# Fri3D_IRA_ESP32.net
KiCad netlist of a schematic drawn in Altium Designer
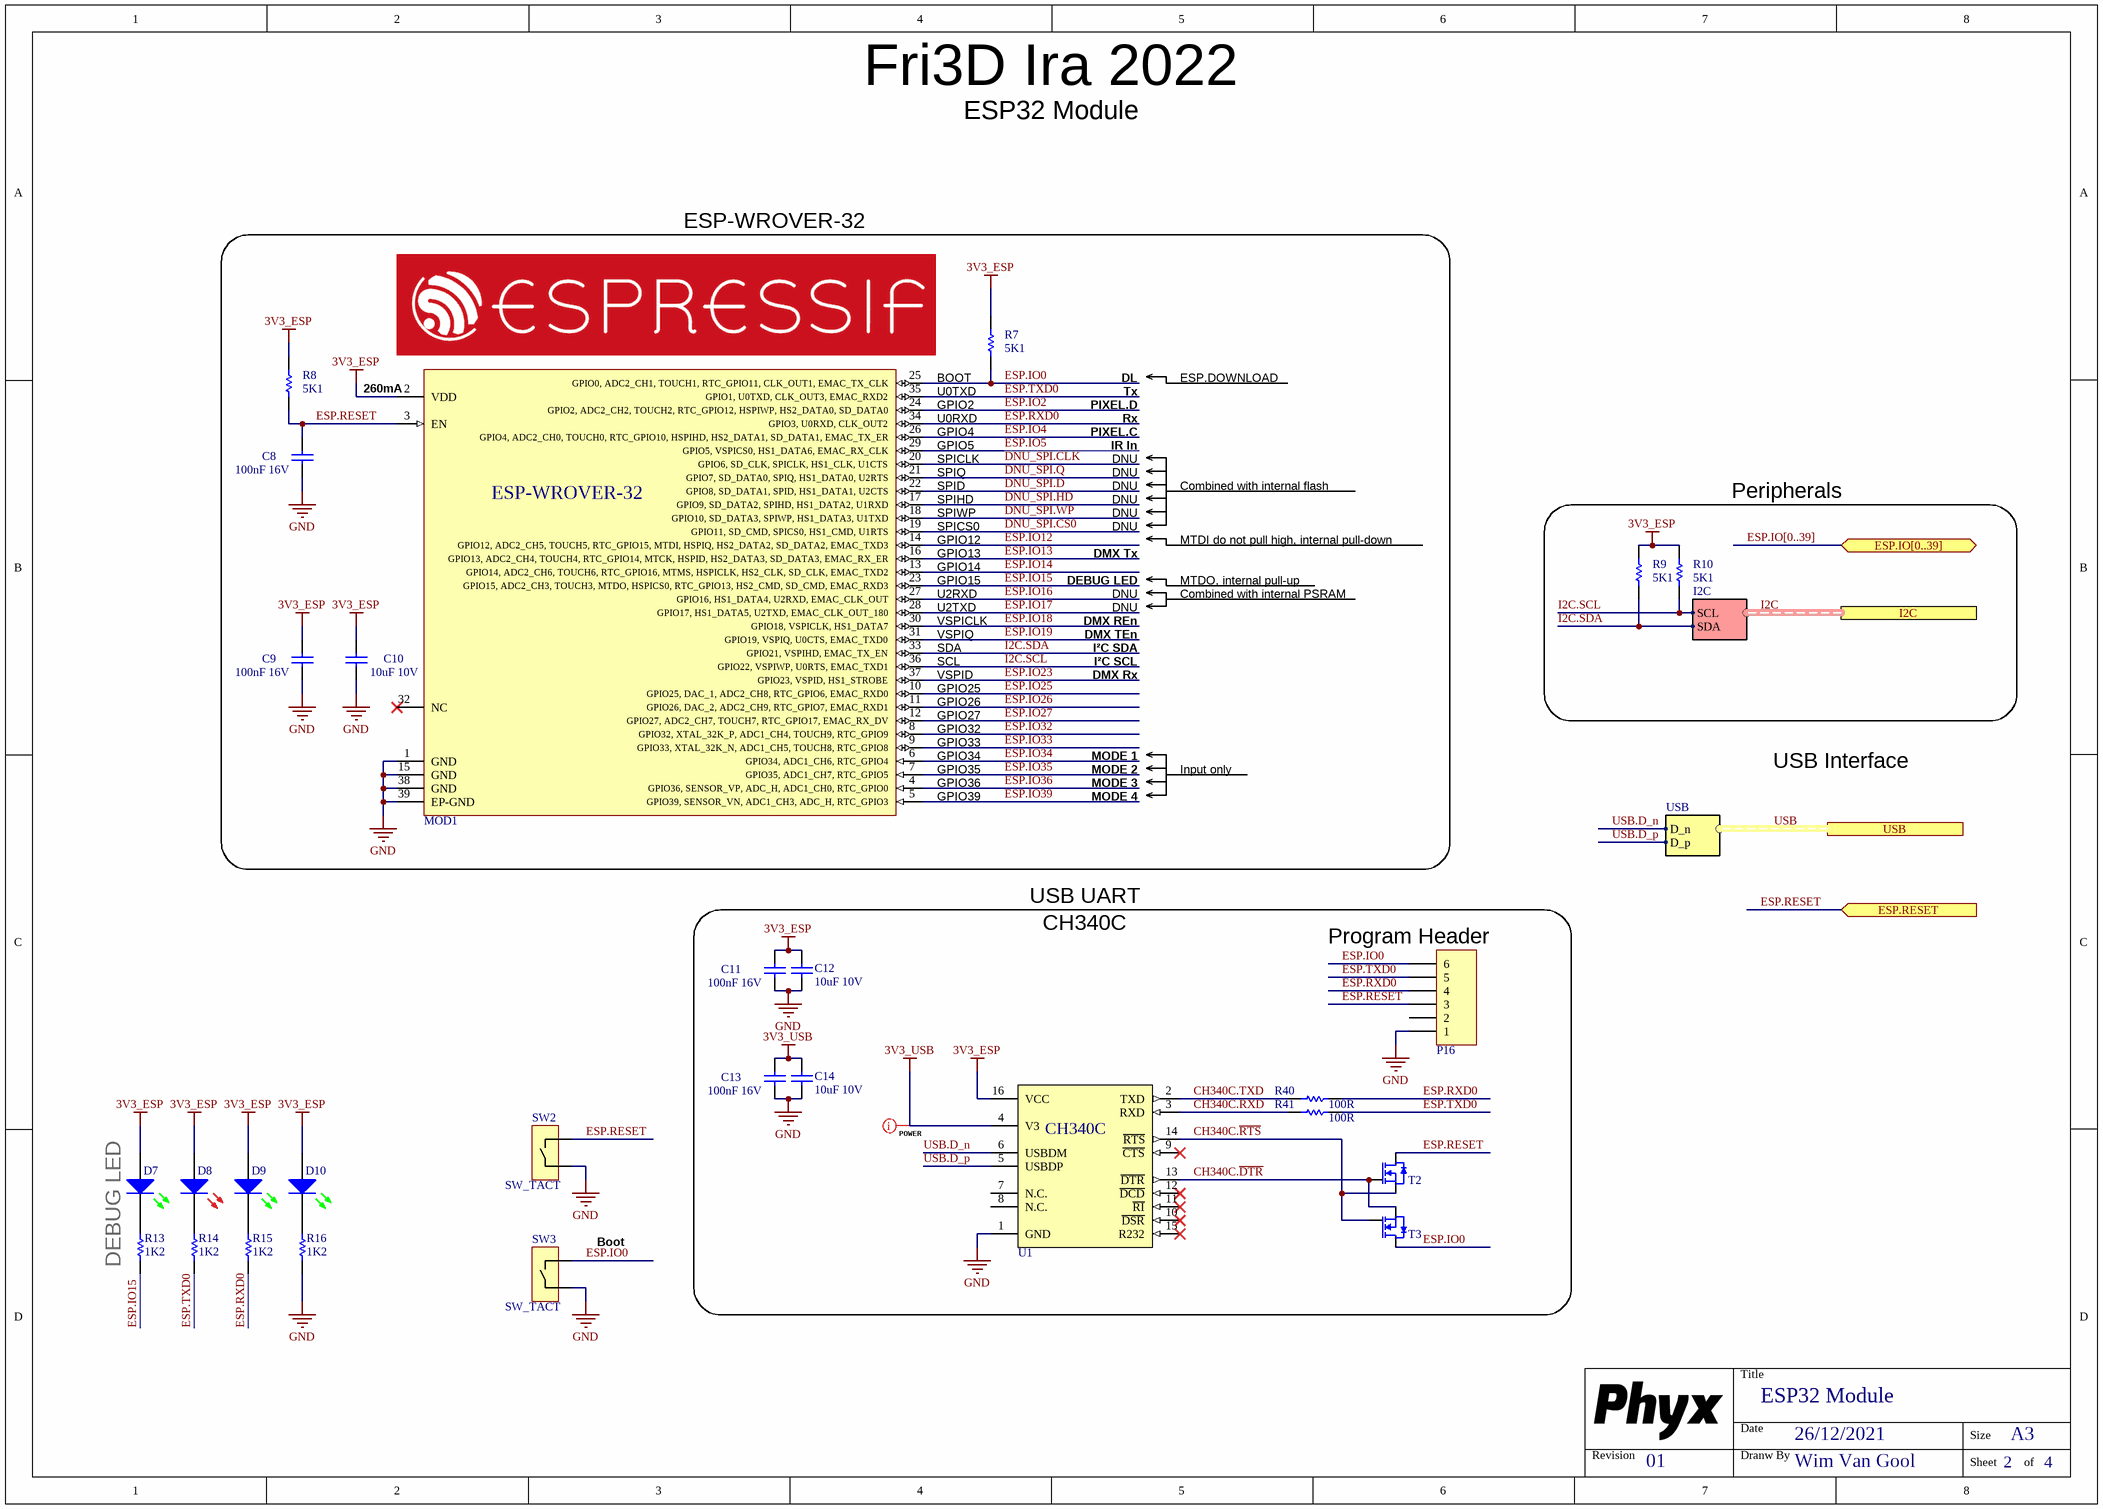
[diagram p0: Fri3D_IRA_ESP32.SchDoc]

(export (version "E")
  (design (tool "Eeschema 10.0.6"))
  (components
    (comp (ref "C8")
      (value "100nF 16V")
      (footprint "C0603_N")
      (description "Capacitor Ceramic")
      (libsource (lib "Phyx_Components") (part "CAP_CERAMIC"))
    )
    (comp (ref "C9")
      (value "100nF 16V")
      (footprint "C0603_N")
      (description "Capacitor Ceramic")
      (libsource (lib "Phyx_Components") (part "CAP_CERAMIC"))
    )
    (comp (ref "C10")
      (value "10uF 10V")
      (footprint "C0805_N")
      (description "Capacitor Ceramic")
      (fields (field (name "Comment") "CAP_CERAMIC"))
      (libsource (lib "Phyx_Components") (part "CAP_CERAMIC"))
    )
    (comp (ref "C11")
      (value "100nF 16V")
      (footprint "C0603_N")
      (description "Capacitor Ceramic")
      (libsource (lib "Phyx_Components") (part "CAP_CERAMIC"))
    )
    (comp (ref "C12")
      (value "10uF 10V")
      (footprint "C0805_N")
      (description "Capacitor Ceramic")
      (fields (field (name "Comment") "CAP_CERAMIC"))
      (libsource (lib "Phyx_Components") (part "CAP_CERAMIC"))
    )
    (comp (ref "C13")
      (value "100nF 16V")
      (footprint "C0603_N")
      (description "Capacitor Ceramic")
      (libsource (lib "Phyx_Components") (part "CAP_CERAMIC"))
    )
    (comp (ref "C14")
      (value "10uF 10V")
      (footprint "C0805_N")
      (description "Capacitor Ceramic")
      (fields (field (name "Comment") "CAP_CERAMIC"))
      (libsource (lib "Phyx_Components") (part "CAP_CERAMIC"))
    )
    (comp (ref "D7")
      (value "Default 0805 Green LED")
      (footprint "LED_0805_GR")
      (description "=Description")
      (libsource (lib "Phyx_Components") (part "LED_GREEN"))
    )
    (comp (ref "D8")
      (value "Default 0805 Red LED")
      (footprint "LED_0805_RD")
      (description "=Description")
      (libsource (lib "Phyx_Components") (part "LED_RED"))
    )
    (comp (ref "D9")
      (value "Default 0805 Green LED")
      (footprint "LED_0805_GR")
      (description "=Description")
      (libsource (lib "Phyx_Components") (part "LED_GREEN"))
    )
    (comp (ref "D10")
      (value "Default 0805 Green LED")
      (footprint "LED_0805_GR")
      (description "=Description")
      (libsource (lib "Phyx_Components") (part "LED_GREEN"))
    )
    (comp (ref "MOD1")
      (value "ESP-32 based ESP-WROVER-32")
      (footprint "ESP-WROVER-32")
      (description "WiFi # MOD ESP-WROVER-32")
      (libsource (lib "Phyx_Components") (part "ESP-WROVER-32"))
    )
    (comp (ref "P16")
      (value "Header 6")
      (footprint "HDR1X6")
      (libsource (lib "Phyx_Components") (part "Header 6"))
    )
    (comp (ref "R7")
      (value "5K1")
      (footprint "R0603_N")
      (fields (field (name "Comment") "RESISTOR"))
      (libsource (lib "Phyx_Components") (part "RESISTOR"))
    )
    (comp (ref "R8")
      (value "5K1")
      (footprint "R0603_N")
      (fields (field (name "Comment") "RESISTOR"))
      (libsource (lib "Phyx_Components") (part "RESISTOR"))
    )
    (comp (ref "R9")
      (value "5K1")
      (footprint "R0603_N")
      (fields (field (name "Comment") "RESISTOR"))
      (libsource (lib "Phyx_Components") (part "RESISTOR"))
    )
    (comp (ref "R10")
      (value "5K1")
      (footprint "R0603_N")
      (fields (field (name "Comment") "RESISTOR"))
      (libsource (lib "Phyx_Components") (part "RESISTOR"))
    )
    (comp (ref "R13")
      (value "1K2")
      (footprint "R0603_N")
      (fields (field (name "Comment") "RESISTOR"))
      (libsource (lib "Phyx_Components") (part "RESISTOR"))
    )
    (comp (ref "R14")
      (value "1K2")
      (footprint "R0603_N")
      (fields (field (name "Comment") "RESISTOR"))
      (libsource (lib "Phyx_Components") (part "RESISTOR"))
    )
    (comp (ref "R15")
      (value "1K2")
      (footprint "R0603_N")
      (fields (field (name "Comment") "RESISTOR"))
      (libsource (lib "Phyx_Components") (part "RESISTOR"))
    )
    (comp (ref "R16")
      (value "1K2")
      (footprint "R0603_N")
      (fields (field (name "Comment") "RESISTOR"))
      (libsource (lib "Phyx_Components") (part "RESISTOR"))
    )
    (comp (ref "R40")
      (value "100R")
      (footprint "R0603_N")
      (fields (field (name "Comment") "RESISTOR"))
      (libsource (lib "Phyx_Components") (part "RESISTOR"))
    )
    (comp (ref "R41")
      (value "100R")
      (footprint "R0603_N")
      (fields (field (name "Comment") "RESISTOR"))
      (libsource (lib "Phyx_Components") (part "RESISTOR"))
    )
    (comp (ref "SW2")
      (value "SW_TACT")
      (footprint "WE_430181038816")
      (libsource (lib "Phyx_Components") (part "SW_TACT"))
    )
    (comp (ref "SW3")
      (value "SW_TACT")
      (footprint "WE_430181038816")
      (libsource (lib "Phyx_Components") (part "SW_TACT"))
    )
    (comp (ref "T2")
      (value "0.2A N-Ch MOSFET Vgs 3.2")
      (footprint "SOT23-3")
      (libsource (lib "Phyx_Components") (part "N_MOSFET_GSD"))
    )
    (comp (ref "T3")
      (value "0.2A N-Ch MOSFET Vgs 3.2")
      (footprint "SOT23-3")
      (libsource (lib "Phyx_Components") (part "N_MOSFET_GSD"))
    )
    (comp (ref "U1")
      (value "USB to full UART with internal crystal")
      (footprint "SOIC_N_16")
      (description "=Description")
      (libsource (lib "Phyx_Components") (part "CH340C"))
    )
  )
  (nets
    (net (code "21") (name "/CH340C.RXD") (class "Default")
      (node (ref "R41") (pin "1") (pinfunction "1_1") (pintype "passive"))
      (node (ref "U1") (pin "3") (pinfunction "RXD_3") (pintype "input"))
    )
    (net (code "22") (name "/CH340C.TXD") (class "Default")
      (node (ref "R40") (pin "1") (pinfunction "1_1") (pintype "passive"))
      (node (ref "U1") (pin "2") (pinfunction "TXD_2") (pintype "output"))
    )
    (net (code "23") (name "/CH340C.~{DTR}") (class "Default")
      (node (ref "T2") (pin "1") (pinfunction "G_1") (pintype "passive"))
      (node (ref "T3") (pin "2") (pinfunction "S_2") (pintype "passive"))
      (node (ref "U1") (pin "13") (pinfunction "~{DTR}_13") (pintype "output"))
    )
    (net (code "24") (name "/CH340C.~{RTS}") (class "Default")
      (node (ref "T2") (pin "2") (pinfunction "S_2") (pintype "passive"))
      (node (ref "T3") (pin "1") (pinfunction "G_1") (pintype "passive"))
      (node (ref "U1") (pin "14") (pinfunction "~{RTS}_14") (pintype "output"))
    )
    (net (code "25") (name "/DNU_SPI.CLK") (class "Default")
      (node (ref "MOD1") (pin "20") (pinfunction "GPIO6,_SD_CLK,_SPICLK,_HS1_CLK,_U1CTS_20") (pintype "bidirectional"))
    )
    (net (code "26") (name "/DNU_SPI.CS0") (class "Default")
      (node (ref "MOD1") (pin "19") (pinfunction "GPIO11,_SD_CMD,_SPICS0,_HS1_CMD,_U1RTS_19") (pintype "bidirectional"))
    )
    (net (code "27") (name "/DNU_SPI.D") (class "Default")
      (node (ref "MOD1") (pin "22") (pinfunction "GPIO8,_SD_DATA1,_SPID,_HS1_DATA1,_U2CTS_22") (pintype "bidirectional"))
    )
    (net (code "28") (name "/DNU_SPI.HD") (class "Default")
      (node (ref "MOD1") (pin "17") (pinfunction "GPIO9,_SD_DATA2,_SPIHD,_HS1_DATA2,_U1RXD_17") (pintype "bidirectional"))
    )
    (net (code "29") (name "/DNU_SPI.Q") (class "Default")
      (node (ref "MOD1") (pin "21") (pinfunction "GPIO7,_SD_DATA0,_SPIQ,_HS1_DATA0,_U2RTS_21") (pintype "bidirectional"))
    )
    (net (code "30") (name "/DNU_SPI.WP") (class "Default")
      (node (ref "MOD1") (pin "18") (pinfunction "GPIO10,_SD_DATA3,_SPIWP,_HS1_DATA3,_U1TXD_18") (pintype "bidirectional"))
    )
    (net (code "31") (name "/ESP.IO0") (class "Default")
      (node (ref "MOD1") (pin "25") (pinfunction "GPIO0,_ADC2_CH1,_TOUCH1,_RTC_GPIO11,_CLK_OUT1,_EMAC_TX_CLK_25") (pintype "bidirectional"))
      (node (ref "P16") (pin "6") (pinfunction "6_6") (pintype "passive"))
      (node (ref "R7") (pin "2") (pinfunction "2_2") (pintype "passive"))
      (node (ref "SW3") (pin "1") (pinfunction "1_1") (pintype "passive"))
      (node (ref "T3") (pin "3") (pinfunction "D_3") (pintype "passive"))
    )
    (net (code "32") (name "/ESP.IO2") (class "Default")
      (node (ref "MOD1") (pin "24") (pinfunction "GPIO2,_ADC2_CH2,_TOUCH2,_RTC_GPIO12,_HSPIWP,_HS2_DATA0,_SD_DATA0_24") (pintype "bidirectional"))
    )
    (net (code "33") (name "/ESP.IO4") (class "Default")
      (node (ref "MOD1") (pin "26") (pinfunction "GPIO4,_ADC2_CH0,_TOUCH0,_RTC_GPIO10,_HSPIHD,_HS2_DATA1,_SD_DATA1,_EMAC_TX_ER_26") (pintype "bidirectional"))
    )
    (net (code "34") (name "/ESP.IO5") (class "Default")
      (node (ref "MOD1") (pin "29") (pinfunction "GPIO5,_VSPICS0,_HS1_DATA6,_EMAC_RX_CLK_29") (pintype "bidirectional"))
    )
    (net (code "35") (name "/ESP.IO12") (class "Default")
      (node (ref "MOD1") (pin "14") (pinfunction "GPIO12,_ADC2_CH5,_TOUCH5,_RTC_GPIO15,_MTDI,_HSPIQ,_HS2_DATA2,_SD_DATA2,_EMAC_TXD3_14") (pintype "bidirectional"))
    )
    (net (code "36") (name "/ESP.IO13") (class "Default")
      (node (ref "MOD1") (pin "16") (pinfunction "GPIO13,_ADC2_CH4,_TOUCH4,_RTC_GPIO14,_MTCK,_HSPID,_HS2_DATA3,_SD_DATA3,_EMAC_RX_ER_16") (pintype "bidirectional"))
    )
    (net (code "37") (name "/ESP.IO14") (class "Default")
      (node (ref "MOD1") (pin "13") (pinfunction "GPIO14,_ADC2_CH6,_TOUCH6,_RTC_GPIO16,_MTMS,_HSPICLK,_HS2_CLK,_SD_CLK,_EMAC_TXD2_13") (pintype "bidirectional"))
    )
    (net (code "38") (name "/ESP.IO15") (class "Default")
      (node (ref "MOD1") (pin "23") (pinfunction "GPIO15,_ADC2_CH3,_TOUCH3,_MTDO,_HSPICS0,_RTC_GPIO13,_HS2_CMD,_SD_CMD,_EMAC_RXD3_23") (pintype "bidirectional"))
      (node (ref "R13") (pin "2") (pinfunction "2_2") (pintype "passive"))
    )
    (net (code "39") (name "/ESP.IO16") (class "Default")
      (node (ref "MOD1") (pin "27") (pinfunction "GPIO16,_HS1_DATA4,_U2RXD,_EMAC_CLK_OUT_27") (pintype "bidirectional"))
    )
    (net (code "40") (name "/ESP.IO17") (class "Default")
      (node (ref "MOD1") (pin "28") (pinfunction "GPIO17,_HS1_DATA5,_U2TXD,_EMAC_CLK_OUT_180_28") (pintype "bidirectional"))
    )
    (net (code "41") (name "/ESP.IO18") (class "Default")
      (node (ref "MOD1") (pin "30") (pinfunction "GPIO18,_VSPICLK,_HS1_DATA7_30") (pintype "bidirectional"))
    )
    (net (code "42") (name "/ESP.IO19") (class "Default")
      (node (ref "MOD1") (pin "31") (pinfunction "GPIO19,_VSPIQ,_U0CTS,_EMAC_TXD0_31") (pintype "bidirectional"))
    )
    (net (code "43") (name "/ESP.IO23") (class "Default")
      (node (ref "MOD1") (pin "37") (pinfunction "GPIO23,_VSPID,_HS1_STROBE_37") (pintype "bidirectional"))
    )
    (net (code "44") (name "/ESP.IO25") (class "Default")
      (node (ref "MOD1") (pin "10") (pinfunction "GPIO25,_DAC_1,_ADC2_CH8,_RTC_GPIO6,_EMAC_RXD0_10") (pintype "bidirectional"))
    )
    (net (code "45") (name "/ESP.IO26") (class "Default")
      (node (ref "MOD1") (pin "11") (pinfunction "GPIO26,_DAC_2,_ADC2_CH9,_RTC_GPIO7,_EMAC_RXD1_11") (pintype "bidirectional"))
    )
    (net (code "46") (name "/ESP.IO27") (class "Default")
      (node (ref "MOD1") (pin "12") (pinfunction "GPIO27,_ADC2_CH7,_TOUCH7,_RTC_GPIO17,_EMAC_RX_DV_12") (pintype "bidirectional"))
    )
    (net (code "47") (name "/ESP.IO32") (class "Default")
      (node (ref "MOD1") (pin "8") (pinfunction "GPIO32,_XTAL_32K_P,_ADC1_CH4,_TOUCH9,_RTC_GPIO9_8") (pintype "bidirectional"))
    )
    (net (code "48") (name "/ESP.IO33") (class "Default")
      (node (ref "MOD1") (pin "9") (pinfunction "GPIO33,_XTAL_32K_N,_ADC1_CH5,_TOUCH8,_RTC_GPIO8_9") (pintype "bidirectional"))
    )
    (net (code "49") (name "/ESP.IO34") (class "Default")
      (node (ref "MOD1") (pin "6") (pinfunction "GPIO34,_ADC1_CH6,_RTC_GPIO4_6") (pintype "input"))
    )
    (net (code "50") (name "/ESP.IO35") (class "Default")
      (node (ref "MOD1") (pin "7") (pinfunction "GPIO35,_ADC1_CH7,_RTC_GPIO5_7") (pintype "input"))
    )
    (net (code "51") (name "/ESP.IO36") (class "Default")
      (node (ref "MOD1") (pin "4") (pinfunction "GPIO36,_SENSOR_VP,_ADC_H,_ADC1_CH0,_RTC_GPIO0_4") (pintype "input"))
    )
    (net (code "52") (name "/ESP.IO39") (class "Default")
      (node (ref "MOD1") (pin "5") (pinfunction "GPIO39,_SENSOR_VN,_ADC1_CH3,_ADC_H,_RTC_GPIO3_5") (pintype "input"))
    )
    (net (code "54") (name "/ESP.RESET") (class "Default")
      (node (ref "C8") (pin "1") (pinfunction "1_1") (pintype "passive"))
      (node (ref "MOD1") (pin "3") (pinfunction "EN_3") (pintype "input"))
      (node (ref "P16") (pin "3") (pinfunction "3_3") (pintype "passive"))
      (node (ref "R8") (pin "2") (pinfunction "2_2") (pintype "passive"))
      (node (ref "SW2") (pin "1") (pinfunction "1_1") (pintype "passive"))
      (node (ref "T2") (pin "3") (pinfunction "D_3") (pintype "passive"))
    )
    (net (code "55") (name "/ESP.RXD0") (class "Default")
      (node (ref "MOD1") (pin "34") (pinfunction "GPIO3,_U0RXD,_CLK_OUT2_34") (pintype "bidirectional"))
      (node (ref "P16") (pin "4") (pinfunction "4_4") (pintype "passive"))
      (node (ref "R15") (pin "2") (pinfunction "2_2") (pintype "passive"))
      (node (ref "R40") (pin "2") (pinfunction "2_2") (pintype "passive"))
    )
    (net (code "56") (name "/ESP.TXD0") (class "Default")
      (node (ref "MOD1") (pin "35") (pinfunction "GPIO1,_U0TXD,_CLK_OUT3,_EMAC_RXD2_35") (pintype "bidirectional"))
      (node (ref "P16") (pin "5") (pinfunction "5_5") (pintype "passive"))
      (node (ref "R14") (pin "2") (pinfunction "2_2") (pintype "passive"))
      (node (ref "R41") (pin "2") (pinfunction "2_2") (pintype "passive"))
    )
    (net (code "57") (name "/I2C.SCL") (class "Default")
      (node (ref "MOD1") (pin "36") (pinfunction "GPIO22,_VSPIWP,_U0RTS,_EMAC_TXD1_36") (pintype "bidirectional"))
      (node (ref "R10") (pin "2") (pinfunction "2_2") (pintype "passive"))
    )
    (net (code "58") (name "/I2C.SDA") (class "Default")
      (node (ref "MOD1") (pin "33") (pinfunction "GPIO21,_VSPIHD,_EMAC_TX_EN_33") (pintype "bidirectional"))
      (node (ref "R9") (pin "2") (pinfunction "2_2") (pintype "passive"))
    )
    (net (code "60") (name "/USB.D_n") (class "Default")
      (node (ref "U1") (pin "6") (pinfunction "USBDM_6") (pintype "passive"))
    )
    (net (code "61") (name "/USB.D_p") (class "Default")
      (node (ref "U1") (pin "5") (pinfunction "USBDP_5") (pintype "passive"))
    )
    (net (code "63") (name "3V3_ESP") (class "Default")
      (node (ref "C10") (pin "1") (pinfunction "1_1") (pintype "passive"))
      (node (ref "C11") (pin "1") (pinfunction "1_1") (pintype "passive"))
      (node (ref "C12") (pin "2") (pinfunction "2_2") (pintype "passive"))
      (node (ref "C9") (pin "1") (pinfunction "1_1") (pintype "passive"))
      (node (ref "D10") (pin "1") (pinfunction "A_1") (pintype "passive"))
      (node (ref "D7") (pin "1") (pinfunction "A_1") (pintype "passive"))
      (node (ref "D8") (pin "1") (pinfunction "A_1") (pintype "passive"))
      (node (ref "D9") (pin "1") (pinfunction "A_1") (pintype "passive"))
      (node (ref "MOD1") (pin "2") (pinfunction "VDD_2") (pintype "power_in"))
      (node (ref "R10") (pin "1") (pinfunction "1_1") (pintype "passive"))
      (node (ref "R7") (pin "1") (pinfunction "1_1") (pintype "passive"))
      (node (ref "R8") (pin "1") (pinfunction "1_1") (pintype "passive"))
      (node (ref "R9") (pin "1") (pinfunction "1_1") (pintype "passive"))
      (node (ref "U1") (pin "16") (pinfunction "VCC_16") (pintype "power_in"))
    )
    (net (code "64") (name "3V3_USB") (class "Default")
      (node (ref "C13") (pin "1") (pinfunction "1_1") (pintype "passive"))
      (node (ref "C14") (pin "2") (pinfunction "2_2") (pintype "passive"))
      (node (ref "U1") (pin "4") (pinfunction "V3_4") (pintype "power_in"))
    )
    (net (code "65") (name "GND") (class "Default")
      (node (ref "C10") (pin "2") (pinfunction "2_2") (pintype "passive"))
      (node (ref "C11") (pin "2") (pinfunction "2_2") (pintype "passive"))
      (node (ref "C12") (pin "1") (pinfunction "1_1") (pintype "passive"))
      (node (ref "C13") (pin "2") (pinfunction "2_2") (pintype "passive"))
      (node (ref "C14") (pin "1") (pinfunction "1_1") (pintype "passive"))
      (node (ref "C8") (pin "2") (pinfunction "2_2") (pintype "passive"))
      (node (ref "C9") (pin "2") (pinfunction "2_2") (pintype "passive"))
      (node (ref "MOD1") (pin "1") (pinfunction "GND_1") (pintype "power_in"))
      (node (ref "MOD1") (pin "15") (pinfunction "GND_15") (pintype "power_in"))
      (node (ref "MOD1") (pin "38") (pinfunction "GND_38") (pintype "power_in"))
      (node (ref "MOD1") (pin "39") (pinfunction "EP-GND_39") (pintype "power_in"))
      (node (ref "P16") (pin "1") (pinfunction "1_1") (pintype "passive"))
      (node (ref "R16") (pin "2") (pinfunction "2_2") (pintype "passive"))
      (node (ref "SW2") (pin "2") (pinfunction "2_2") (pintype "passive"))
      (node (ref "SW3") (pin "2") (pinfunction "2_2") (pintype "passive"))
      (node (ref "U1") (pin "1") (pinfunction "GND_1") (pintype "power_in"))
    )
    (net (code "66") (name "Net-(D7-K)") (class "Default")
      (node (ref "D7") (pin "2") (pinfunction "K_2") (pintype "passive"))
      (node (ref "R13") (pin "1") (pinfunction "1_1") (pintype "passive"))
    )
    (net (code "67") (name "Net-(D8-K)") (class "Default")
      (node (ref "D8") (pin "2") (pinfunction "K_2") (pintype "passive"))
      (node (ref "R14") (pin "1") (pinfunction "1_1") (pintype "passive"))
    )
    (net (code "68") (name "Net-(D9-K)") (class "Default")
      (node (ref "D9") (pin "2") (pinfunction "K_2") (pintype "passive"))
      (node (ref "R15") (pin "1") (pinfunction "1_1") (pintype "passive"))
    )
    (net (code "69") (name "Net-(D10-K)") (class "Default")
      (node (ref "D10") (pin "2") (pinfunction "K_2") (pintype "passive"))
      (node (ref "R16") (pin "1") (pinfunction "1_1") (pintype "passive"))
    )
    (net (code "70") (name "unconnected-(MOD1-NC-Pad32)") (class "Default")
      (node (ref "MOD1") (pin "32") (pinfunction "NC_32") (pintype "passive+no_connect"))
    )
    (net (code "71") (name "unconnected-(P16-Pad2)") (class "Default")
      (node (ref "P16") (pin "2") (pinfunction "2_2") (pintype "passive"))
    )
    (net (code "72") (name "unconnected-(U1-N.C.-Pad7)") (class "Default")
      (node (ref "U1") (pin "7") (pinfunction "N.C._7") (pintype "passive"))
    )
    (net (code "73") (name "unconnected-(U1-N.C.-Pad8)") (class "Default")
      (node (ref "U1") (pin "8") (pinfunction "N.C._8") (pintype "passive"))
    )
    (net (code "74") (name "unconnected-(U1-R232-Pad15)") (class "Default")
      (node (ref "U1") (pin "15") (pinfunction "R232_15") (pintype "input+no_connect"))
    )
    (net (code "75") (name "unconnected-(U1-~{CTS}-Pad9)") (class "Default")
      (node (ref "U1") (pin "9") (pinfunction "~{CTS}_9") (pintype "input+no_connect"))
    )
    (net (code "76") (name "unconnected-(U1-~{DCD}-Pad12)") (class "Default")
      (node (ref "U1") (pin "12") (pinfunction "~{DCD}_12") (pintype "input+no_connect"))
    )
    (net (code "77") (name "unconnected-(U1-~{DSR}-Pad10)") (class "Default")
      (node (ref "U1") (pin "10") (pinfunction "~{DSR}_10") (pintype "input+no_connect"))
    )
    (net (code "78") (name "unconnected-(U1-~{RI}-Pad11)") (class "Default")
      (node (ref "U1") (pin "11") (pinfunction "~{RI}_11") (pintype "input+no_connect"))
    )
  )
)
